# L000-Power.net
KiCad netlist of a schematic drawn in EAGLE
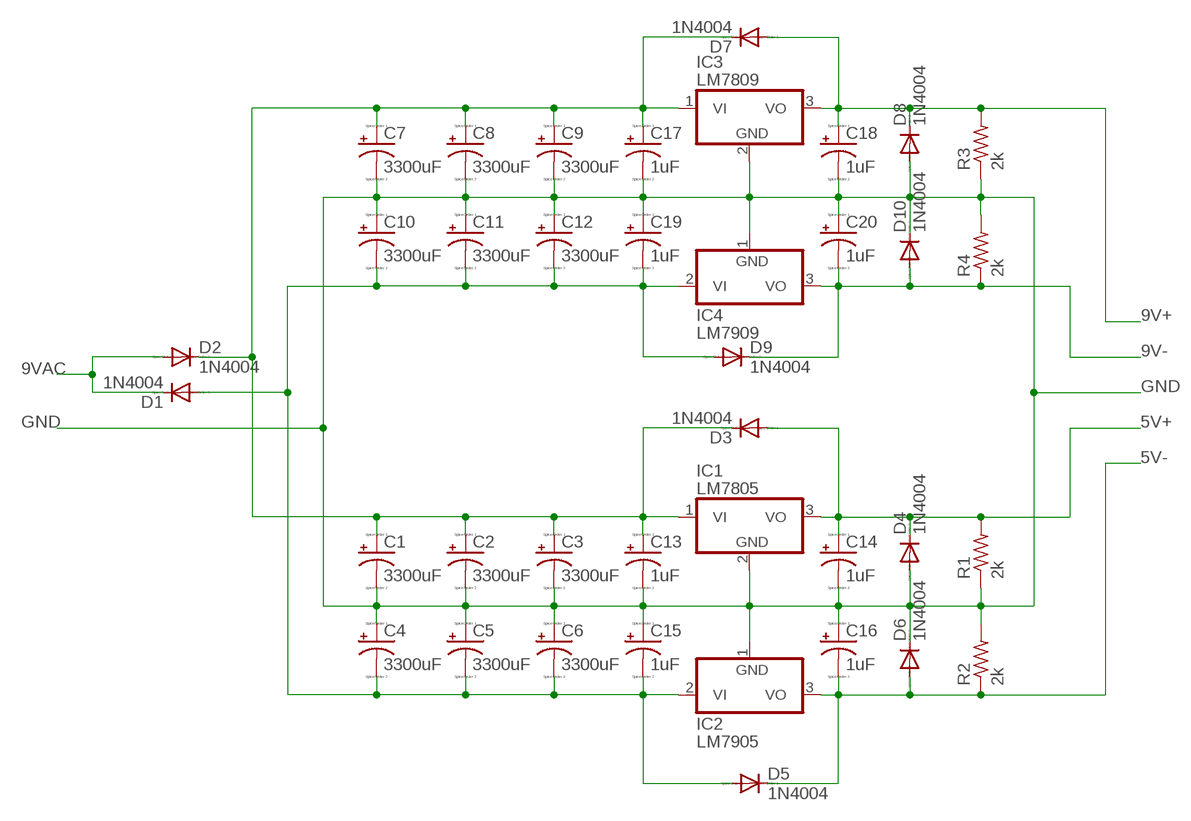
[diagram p0: schematic, sheet 1]

(export (version "E")
  (design (tool "Eeschema 10.0.6"))
  (components
    (comp (ref "C1")
      (value "3300uF")
      (footprint "eagle-import:E5-13")
      (libsource (lib "eagle-import") (part "CPOL-USE5-13"))
    )
    (comp (ref "C2")
      (value "3300uF")
      (footprint "eagle-import:E5-13")
      (libsource (lib "eagle-import") (part "CPOL-USE5-13"))
    )
    (comp (ref "C3")
      (value "3300uF")
      (footprint "eagle-import:E5-13")
      (libsource (lib "eagle-import") (part "CPOL-USE5-13"))
    )
    (comp (ref "C4")
      (value "3300uF")
      (footprint "eagle-import:E5-13")
      (libsource (lib "eagle-import") (part "CPOL-USE5-13"))
    )
    (comp (ref "C5")
      (value "3300uF")
      (footprint "eagle-import:E5-13")
      (libsource (lib "eagle-import") (part "CPOL-USE5-13"))
    )
    (comp (ref "C6")
      (value "3300uF")
      (footprint "eagle-import:E5-13")
      (libsource (lib "eagle-import") (part "CPOL-USE5-13"))
    )
    (comp (ref "C7")
      (value "3300uF")
      (footprint "eagle-import:E5-13")
      (libsource (lib "eagle-import") (part "CPOL-USE5-13"))
    )
    (comp (ref "C8")
      (value "3300uF")
      (footprint "eagle-import:E5-13")
      (libsource (lib "eagle-import") (part "CPOL-USE5-13"))
    )
    (comp (ref "C9")
      (value "3300uF")
      (footprint "eagle-import:E5-13")
      (libsource (lib "eagle-import") (part "CPOL-USE5-13"))
    )
    (comp (ref "C10")
      (value "3300uF")
      (footprint "eagle-import:E5-13")
      (libsource (lib "eagle-import") (part "CPOL-USE5-13"))
    )
    (comp (ref "C11")
      (value "3300uF")
      (footprint "eagle-import:E5-13")
      (libsource (lib "eagle-import") (part "CPOL-USE5-13"))
    )
    (comp (ref "C12")
      (value "3300uF")
      (footprint "eagle-import:E5-13")
      (libsource (lib "eagle-import") (part "CPOL-USE5-13"))
    )
    (comp (ref "C13")
      (value "1uF")
      (footprint "eagle-import:E5-13")
      (libsource (lib "eagle-import") (part "CPOL-USE5-13"))
    )
    (comp (ref "C14")
      (value "1uF")
      (footprint "eagle-import:E5-13")
      (libsource (lib "eagle-import") (part "CPOL-USE5-13"))
    )
    (comp (ref "C15")
      (value "1uF")
      (footprint "eagle-import:E5-13")
      (libsource (lib "eagle-import") (part "CPOL-USE5-13"))
    )
    (comp (ref "C16")
      (value "1uF")
      (footprint "eagle-import:E5-13")
      (libsource (lib "eagle-import") (part "CPOL-USE5-13"))
    )
    (comp (ref "C17")
      (value "1uF")
      (footprint "eagle-import:E5-13")
      (libsource (lib "eagle-import") (part "CPOL-USE5-13"))
    )
    (comp (ref "C18")
      (value "1uF")
      (footprint "eagle-import:E5-13")
      (libsource (lib "eagle-import") (part "CPOL-USE5-13"))
    )
    (comp (ref "C19")
      (value "1uF")
      (footprint "eagle-import:E5-13")
      (libsource (lib "eagle-import") (part "CPOL-USE5-13"))
    )
    (comp (ref "C20")
      (value "1uF")
      (footprint "eagle-import:E5-13")
      (libsource (lib "eagle-import") (part "CPOL-USE5-13"))
    )
    (comp (ref "D1")
      (value "1N4004")
      (footprint "eagle-import:DO41-10")
      (libsource (lib "eagle-import") (part "1N4004"))
    )
    (comp (ref "D2")
      (value "1N4004")
      (footprint "eagle-import:DO41-10")
      (libsource (lib "eagle-import") (part "1N4004"))
    )
    (comp (ref "D3")
      (value "1N4004")
      (footprint "eagle-import:DO41-10")
      (libsource (lib "eagle-import") (part "1N4004"))
    )
    (comp (ref "D4")
      (value "1N4004")
      (footprint "eagle-import:DO41-10")
      (libsource (lib "eagle-import") (part "1N4004"))
    )
    (comp (ref "D5")
      (value "1N4004")
      (footprint "eagle-import:DO41-10")
      (libsource (lib "eagle-import") (part "1N4004"))
    )
    (comp (ref "D6")
      (value "1N4004")
      (footprint "eagle-import:DO41-10")
      (libsource (lib "eagle-import") (part "1N4004"))
    )
    (comp (ref "D7")
      (value "1N4004")
      (footprint "eagle-import:DO41-10")
      (libsource (lib "eagle-import") (part "1N4004"))
    )
    (comp (ref "D8")
      (value "1N4004")
      (footprint "eagle-import:DO41-10")
      (libsource (lib "eagle-import") (part "1N4004"))
    )
    (comp (ref "D9")
      (value "1N4004")
      (footprint "eagle-import:DO41-10")
      (libsource (lib "eagle-import") (part "1N4004"))
    )
    (comp (ref "D10")
      (value "1N4004")
      (footprint "eagle-import:DO41-10")
      (libsource (lib "eagle-import") (part "1N4004"))
    )
    (comp (ref "IC1")
      (value "LM7805")
      (footprint "eagle-import:TO220H")
      (libsource (lib "eagle-import") (part "78T05"))
    )
    (comp (ref "IC2")
      (value "LM7905")
      (footprint "eagle-import:TO220H")
      (libsource (lib "eagle-import") (part "79T05"))
    )
    (comp (ref "IC3")
      (value "LM7809")
      (footprint "eagle-import:TO220H")
      (libsource (lib "eagle-import") (part "78T08"))
    )
    (comp (ref "IC4")
      (value "LM7909")
      (footprint "eagle-import:TO220H")
      (libsource (lib "eagle-import") (part "79T08"))
    )
    (comp (ref "R1")
      (value "2k")
      (footprint "eagle-import:0309_10")
      (libsource (lib "eagle-import") (part "R-US_0309/10"))
    )
    (comp (ref "R2")
      (value "2k")
      (footprint "eagle-import:0309_10")
      (libsource (lib "eagle-import") (part "R-US_0309/10"))
    )
    (comp (ref "R3")
      (value "2k")
      (footprint "eagle-import:0309_10")
      (libsource (lib "eagle-import") (part "R-US_0309/10"))
    )
    (comp (ref "R4")
      (value "2k")
      (footprint "eagle-import:0309_10")
      (libsource (lib "eagle-import") (part "R-US_0309/10"))
    )
  )
  (nets
    (net (code "1") (name "/5V+") (class "Default")
      (node (ref "C14") (pin "+") (pinfunction "+_+") (pintype "passive"))
      (node (ref "D3") (pin "A") (pinfunction "A_A") (pintype "passive"))
      (node (ref "D4") (pin "C") (pinfunction "C_C") (pintype "passive"))
      (node (ref "IC1") (pin "3") (pinfunction "VO_3") (pintype "passive"))
      (node (ref "R1") (pin "2") (pinfunction "2_2") (pintype "passive"))
    )
    (net (code "2") (name "/5V-") (class "Default")
      (node (ref "C16") (pin "-") (pinfunction "-_-") (pintype "passive"))
      (node (ref "D5") (pin "C") (pinfunction "C_C") (pintype "passive"))
      (node (ref "D6") (pin "A") (pinfunction "A_A") (pintype "passive"))
      (node (ref "IC2") (pin "3") (pinfunction "VO_3") (pintype "passive"))
      (node (ref "R2") (pin "1") (pinfunction "1_1") (pintype "passive"))
    )
    (net (code "3") (name "/9V+") (class "Default")
      (node (ref "C18") (pin "+") (pinfunction "+_+") (pintype "passive"))
      (node (ref "D7") (pin "A") (pinfunction "A_A") (pintype "passive"))
      (node (ref "D8") (pin "C") (pinfunction "C_C") (pintype "passive"))
      (node (ref "IC3") (pin "3") (pinfunction "VO_3") (pintype "passive"))
      (node (ref "R3") (pin "2") (pinfunction "2_2") (pintype "passive"))
    )
    (net (code "4") (name "/9V-") (class "Default")
      (node (ref "C20") (pin "-") (pinfunction "-_-") (pintype "passive"))
      (node (ref "D10") (pin "A") (pinfunction "A_A") (pintype "passive"))
      (node (ref "D9") (pin "C") (pinfunction "C_C") (pintype "passive"))
      (node (ref "IC4") (pin "3") (pinfunction "VO_3") (pintype "passive"))
      (node (ref "R4") (pin "1") (pinfunction "1_1") (pintype "passive"))
    )
    (net (code "5") (name "/9VAC") (class "Default")
      (node (ref "D1") (pin "C") (pinfunction "C_C") (pintype "passive"))
      (node (ref "D2") (pin "A") (pinfunction "A_A") (pintype "passive"))
    )
    (net (code "6") (name "/GND") (class "Default")
      (node (ref "C1") (pin "-") (pinfunction "-_-") (pintype "passive"))
      (node (ref "C10") (pin "+") (pinfunction "+_+") (pintype "passive"))
      (node (ref "C11") (pin "+") (pinfunction "+_+") (pintype "passive"))
      (node (ref "C12") (pin "+") (pinfunction "+_+") (pintype "passive"))
      (node (ref "C13") (pin "-") (pinfunction "-_-") (pintype "passive"))
      (node (ref "C14") (pin "-") (pinfunction "-_-") (pintype "passive"))
      (node (ref "C15") (pin "+") (pinfunction "+_+") (pintype "passive"))
      (node (ref "C16") (pin "+") (pinfunction "+_+") (pintype "passive"))
      (node (ref "C17") (pin "-") (pinfunction "-_-") (pintype "passive"))
      (node (ref "C18") (pin "-") (pinfunction "-_-") (pintype "passive"))
      (node (ref "C19") (pin "+") (pinfunction "+_+") (pintype "passive"))
      (node (ref "C2") (pin "-") (pinfunction "-_-") (pintype "passive"))
      (node (ref "C20") (pin "+") (pinfunction "+_+") (pintype "passive"))
      (node (ref "C3") (pin "-") (pinfunction "-_-") (pintype "passive"))
      (node (ref "C4") (pin "+") (pinfunction "+_+") (pintype "passive"))
      (node (ref "C5") (pin "+") (pinfunction "+_+") (pintype "passive"))
      (node (ref "C6") (pin "+") (pinfunction "+_+") (pintype "passive"))
      (node (ref "C7") (pin "-") (pinfunction "-_-") (pintype "passive"))
      (node (ref "C8") (pin "-") (pinfunction "-_-") (pintype "passive"))
      (node (ref "C9") (pin "-") (pinfunction "-_-") (pintype "passive"))
      (node (ref "D10") (pin "C") (pinfunction "C_C") (pintype "passive"))
      (node (ref "D4") (pin "A") (pinfunction "A_A") (pintype "passive"))
      (node (ref "D6") (pin "C") (pinfunction "C_C") (pintype "passive"))
      (node (ref "D8") (pin "A") (pinfunction "A_A") (pintype "passive"))
      (node (ref "IC1") (pin "2") (pinfunction "GND_2") (pintype "passive"))
      (node (ref "IC2") (pin "1") (pinfunction "GND_1") (pintype "passive"))
      (node (ref "IC3") (pin "2") (pinfunction "GND_2") (pintype "passive"))
      (node (ref "IC4") (pin "1") (pinfunction "GND_1") (pintype "passive"))
      (node (ref "R1") (pin "1") (pinfunction "1_1") (pintype "passive"))
      (node (ref "R2") (pin "2") (pinfunction "2_2") (pintype "passive"))
      (node (ref "R3") (pin "1") (pinfunction "1_1") (pintype "passive"))
      (node (ref "R4") (pin "2") (pinfunction "2_2") (pintype "passive"))
    )
    (net (code "7") (name "Net-(IC1-VI)") (class "Default")
      (node (ref "C1") (pin "+") (pinfunction "+_+") (pintype "passive"))
      (node (ref "C13") (pin "+") (pinfunction "+_+") (pintype "passive"))
      (node (ref "C17") (pin "+") (pinfunction "+_+") (pintype "passive"))
      (node (ref "C2") (pin "+") (pinfunction "+_+") (pintype "passive"))
      (node (ref "C3") (pin "+") (pinfunction "+_+") (pintype "passive"))
      (node (ref "C7") (pin "+") (pinfunction "+_+") (pintype "passive"))
      (node (ref "C8") (pin "+") (pinfunction "+_+") (pintype "passive"))
      (node (ref "C9") (pin "+") (pinfunction "+_+") (pintype "passive"))
      (node (ref "D2") (pin "C") (pinfunction "C_C") (pintype "passive"))
      (node (ref "D3") (pin "C") (pinfunction "C_C") (pintype "passive"))
      (node (ref "D7") (pin "C") (pinfunction "C_C") (pintype "passive"))
      (node (ref "IC1") (pin "1") (pinfunction "VI_1") (pintype "input"))
      (node (ref "IC3") (pin "1") (pinfunction "VI_1") (pintype "input"))
    )
    (net (code "8") (name "Net-(IC2-VI)") (class "Default")
      (node (ref "C10") (pin "-") (pinfunction "-_-") (pintype "passive"))
      (node (ref "C11") (pin "-") (pinfunction "-_-") (pintype "passive"))
      (node (ref "C12") (pin "-") (pinfunction "-_-") (pintype "passive"))
      (node (ref "C15") (pin "-") (pinfunction "-_-") (pintype "passive"))
      (node (ref "C19") (pin "-") (pinfunction "-_-") (pintype "passive"))
      (node (ref "C4") (pin "-") (pinfunction "-_-") (pintype "passive"))
      (node (ref "C5") (pin "-") (pinfunction "-_-") (pintype "passive"))
      (node (ref "C6") (pin "-") (pinfunction "-_-") (pintype "passive"))
      (node (ref "D1") (pin "A") (pinfunction "A_A") (pintype "passive"))
      (node (ref "D5") (pin "A") (pinfunction "A_A") (pintype "passive"))
      (node (ref "D9") (pin "A") (pinfunction "A_A") (pintype "passive"))
      (node (ref "IC2") (pin "2") (pinfunction "VI_2") (pintype "input"))
      (node (ref "IC4") (pin "2") (pinfunction "VI_2") (pintype "input"))
    )
  )
)
